# Powersupply_V1_10_final.net
KiCad netlist of a schematic drawn in EAGLE
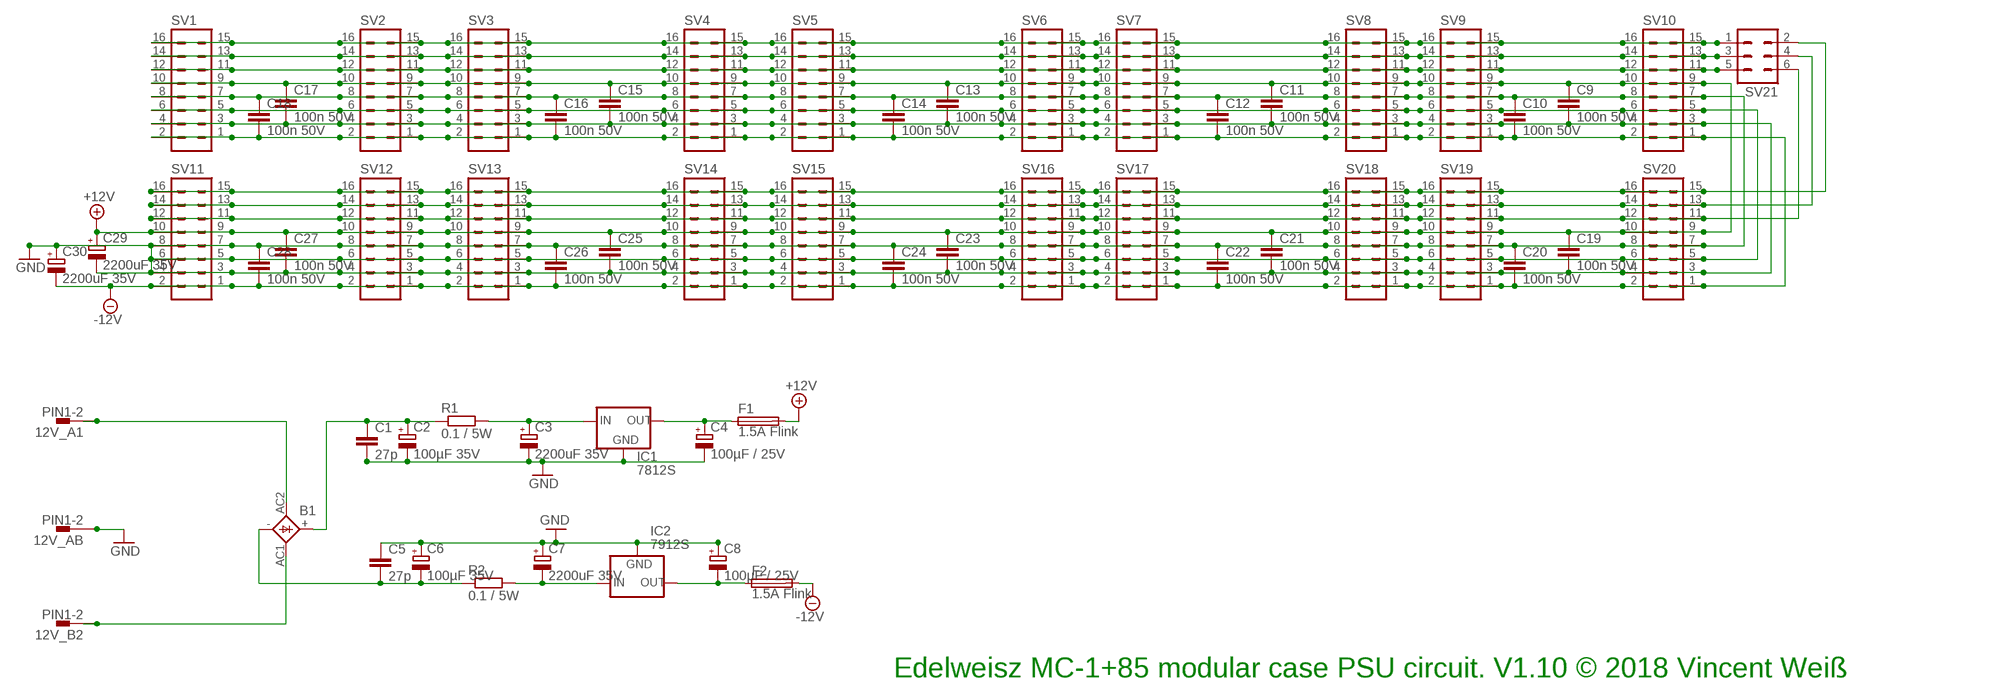
[diagram p0: schematic, sheet 1]

(export (version "E")
  (design (tool "Eeschema 10.0.6"))
  (components
    (comp (ref "12V_A1")
      (value "PIN1-2")
      (footprint "eagle-import:62221")
      (fields (field (name "MF") "TYCO ELECTRONICS") (field (name "MPN") "62221-1"))
      (libsource (lib "eagle-import") (part "PIN1-2"))
    )
    (comp (ref "12V_AB")
      (value "PIN1-2")
      (footprint "eagle-import:62221")
      (fields (field (name "MF") "TYCO ELECTRONICS") (field (name "MPN") "62221-1"))
      (libsource (lib "eagle-import") (part "PIN1-2"))
    )
    (comp (ref "12V_B2")
      (value "PIN1-2")
      (footprint "eagle-import:62221")
      (fields (field (name "MF") "TYCO ELECTRONICS") (field (name "MPN") "62221-1"))
      (libsource (lib "eagle-import") (part "PIN1-2"))
    )
    (comp (ref "B1")
      (value "GBU4")
      (footprint "eagle-import:GBU4S")
      (libsource (lib "eagle-import") (part "GBU4"))
    )
    (comp (ref "C1")
      (value "27p")
      (footprint "eagle-import:C050-024X044")
      (libsource (lib "eagle-import") (part "C-EU050-024X044"))
    )
    (comp (ref "C2")
      (value "100µF 35V")
      (footprint "eagle-import:E2,5-7")
      (libsource (lib "eagle-import") (part "CPOL-EUE2.5-7"))
    )
    (comp (ref "C3")
      (value "2200uF 35V")
      (footprint "eagle-import:E7,5-16")
      (libsource (lib "eagle-import") (part "CPOL-EUE7.5-16"))
    )
    (comp (ref "C4")
      (value "100µF / 25V")
      (footprint "eagle-import:E2,5-7")
      (libsource (lib "eagle-import") (part "CPOL-EUE2.5-7"))
    )
    (comp (ref "C5")
      (value "27p")
      (footprint "eagle-import:C050-024X044")
      (libsource (lib "eagle-import") (part "C-EU050-024X044"))
    )
    (comp (ref "C6")
      (value "100µF 35V")
      (footprint "eagle-import:E2,5-7")
      (libsource (lib "eagle-import") (part "CPOL-EUE2.5-7"))
    )
    (comp (ref "C7")
      (value "2200uF 35V")
      (footprint "eagle-import:E7,5-16")
      (libsource (lib "eagle-import") (part "CPOL-EUE7.5-16"))
    )
    (comp (ref "C8")
      (value "100µF / 25V")
      (footprint "eagle-import:E2,5-7")
      (libsource (lib "eagle-import") (part "CPOL-EUE2.5-7"))
    )
    (comp (ref "C9")
      (value "100n 50V")
      (footprint "eagle-import:C025-025X050")
      (libsource (lib "eagle-import") (part "C-EU025-025X050"))
    )
    (comp (ref "C10")
      (value "100n 50V")
      (footprint "eagle-import:C025-025X050")
      (libsource (lib "eagle-import") (part "C-EU025-025X050"))
    )
    (comp (ref "C11")
      (value "100n 50V")
      (footprint "eagle-import:C025-025X050")
      (libsource (lib "eagle-import") (part "C-EU025-025X050"))
    )
    (comp (ref "C12")
      (value "100n 50V")
      (footprint "eagle-import:C025-025X050")
      (libsource (lib "eagle-import") (part "C-EU025-025X050"))
    )
    (comp (ref "C13")
      (value "100n 50V")
      (footprint "eagle-import:C025-025X050")
      (libsource (lib "eagle-import") (part "C-EU025-025X050"))
    )
    (comp (ref "C14")
      (value "100n 50V")
      (footprint "eagle-import:C025-025X050")
      (libsource (lib "eagle-import") (part "C-EU025-025X050"))
    )
    (comp (ref "C15")
      (value "100n 50V")
      (footprint "eagle-import:C025-025X050")
      (libsource (lib "eagle-import") (part "C-EU025-025X050"))
    )
    (comp (ref "C16")
      (value "100n 50V")
      (footprint "eagle-import:C025-025X050")
      (libsource (lib "eagle-import") (part "C-EU025-025X050"))
    )
    (comp (ref "C17")
      (value "100n 50V")
      (footprint "eagle-import:C025-025X050")
      (libsource (lib "eagle-import") (part "C-EU025-025X050"))
    )
    (comp (ref "C18")
      (value "100n 50V")
      (footprint "eagle-import:C025-025X050")
      (libsource (lib "eagle-import") (part "C-EU025-025X050"))
    )
    (comp (ref "C19")
      (value "100n 50V")
      (footprint "eagle-import:C025-025X050")
      (libsource (lib "eagle-import") (part "C-EU025-025X050"))
    )
    (comp (ref "C20")
      (value "100n 50V")
      (footprint "eagle-import:C025-025X050")
      (libsource (lib "eagle-import") (part "C-EU025-025X050"))
    )
    (comp (ref "C21")
      (value "100n 50V")
      (footprint "eagle-import:C025-025X050")
      (libsource (lib "eagle-import") (part "C-EU025-025X050"))
    )
    (comp (ref "C22")
      (value "100n 50V")
      (footprint "eagle-import:C025-025X050")
      (libsource (lib "eagle-import") (part "C-EU025-025X050"))
    )
    (comp (ref "C23")
      (value "100n 50V")
      (footprint "eagle-import:C025-025X050")
      (libsource (lib "eagle-import") (part "C-EU025-025X050"))
    )
    (comp (ref "C24")
      (value "100n 50V")
      (footprint "eagle-import:C025-025X050")
      (libsource (lib "eagle-import") (part "C-EU025-025X050"))
    )
    (comp (ref "C25")
      (value "100n 50V")
      (footprint "eagle-import:C025-025X050")
      (libsource (lib "eagle-import") (part "C-EU025-025X050"))
    )
    (comp (ref "C26")
      (value "100n 50V")
      (footprint "eagle-import:C025-025X050")
      (libsource (lib "eagle-import") (part "C-EU025-025X050"))
    )
    (comp (ref "C27")
      (value "100n 50V")
      (footprint "eagle-import:C025-025X050")
      (libsource (lib "eagle-import") (part "C-EU025-025X050"))
    )
    (comp (ref "C28")
      (value "100n 50V")
      (footprint "eagle-import:C025-025X050")
      (libsource (lib "eagle-import") (part "C-EU025-025X050"))
    )
    (comp (ref "C29")
      (value "2200uF 35V")
      (footprint "eagle-import:E7,5-16")
      (libsource (lib "eagle-import") (part "CPOL-EUE7.5-16"))
    )
    (comp (ref "C30")
      (value "2200uF 35V")
      (footprint "eagle-import:E7,5-16")
      (libsource (lib "eagle-import") (part "CPOL-EUE7.5-16"))
    )
    (comp (ref "F1")
      (value "1.5A Flink")
      (footprint "eagle-import:SH22,5")
      (fields (field (name "MF") "SCHURTER") (field (name "MPN") "0031.8201"))
      (libsource (lib "eagle-import") (part "SH22,5"))
    )
    (comp (ref "F2")
      (value "1.5A Flink")
      (footprint "eagle-import:SH22,5")
      (fields (field (name "MF") "SCHURTER") (field (name "MPN") "0031.8201"))
      (libsource (lib "eagle-import") (part "SH22,5"))
    )
    (comp (ref "IC1")
      (value "7812S")
      (footprint "eagle-import:78XXS")
      (libsource (lib "eagle-import") (part "78XXS"))
    )
    (comp (ref "IC2")
      (value "7912S")
      (footprint "eagle-import:79XXS")
      (libsource (lib "eagle-import") (part "79XXS"))
    )
    (comp (ref "R1")
      (value "0.1 / 5W")
      (footprint "eagle-import:P0613_15")
      (libsource (lib "eagle-import") (part "R-EU_0613/15"))
    )
    (comp (ref "R2")
      (value "0.1 / 5W")
      (footprint "eagle-import:P0613_15")
      (libsource (lib "eagle-import") (part "R-EU_0613/15"))
    )
    (comp (ref "SV1")
      (value "ML16")
      (footprint "eagle-import:ML16")
      (libsource (lib "eagle-import") (part "ML16"))
    )
    (comp (ref "SV2")
      (value "ML16")
      (footprint "eagle-import:ML16")
      (libsource (lib "eagle-import") (part "ML16"))
    )
    (comp (ref "SV3")
      (value "ML16")
      (footprint "eagle-import:ML16")
      (libsource (lib "eagle-import") (part "ML16"))
    )
    (comp (ref "SV4")
      (value "ML16")
      (footprint "eagle-import:ML16")
      (libsource (lib "eagle-import") (part "ML16"))
    )
    (comp (ref "SV5")
      (value "ML16")
      (footprint "eagle-import:ML16")
      (libsource (lib "eagle-import") (part "ML16"))
    )
    (comp (ref "SV6")
      (value "ML16")
      (footprint "eagle-import:ML16")
      (libsource (lib "eagle-import") (part "ML16"))
    )
    (comp (ref "SV7")
      (value "ML16")
      (footprint "eagle-import:ML16")
      (libsource (lib "eagle-import") (part "ML16"))
    )
    (comp (ref "SV8")
      (value "ML16")
      (footprint "eagle-import:ML16")
      (libsource (lib "eagle-import") (part "ML16"))
    )
    (comp (ref "SV9")
      (value "ML16")
      (footprint "eagle-import:ML16")
      (libsource (lib "eagle-import") (part "ML16"))
    )
    (comp (ref "SV10")
      (value "ML16")
      (footprint "eagle-import:ML16")
      (libsource (lib "eagle-import") (part "ML16"))
    )
    (comp (ref "SV11")
      (value "ML16")
      (footprint "eagle-import:ML16")
      (libsource (lib "eagle-import") (part "ML16"))
    )
    (comp (ref "SV12")
      (value "ML16")
      (footprint "eagle-import:ML16")
      (libsource (lib "eagle-import") (part "ML16"))
    )
    (comp (ref "SV13")
      (value "ML16")
      (footprint "eagle-import:ML16")
      (libsource (lib "eagle-import") (part "ML16"))
    )
    (comp (ref "SV14")
      (value "ML16")
      (footprint "eagle-import:ML16")
      (libsource (lib "eagle-import") (part "ML16"))
    )
    (comp (ref "SV15")
      (value "ML16")
      (footprint "eagle-import:ML16")
      (libsource (lib "eagle-import") (part "ML16"))
    )
    (comp (ref "SV16")
      (value "ML16")
      (footprint "eagle-import:ML16")
      (libsource (lib "eagle-import") (part "ML16"))
    )
    (comp (ref "SV17")
      (value "ML16")
      (footprint "eagle-import:ML16")
      (libsource (lib "eagle-import") (part "ML16"))
    )
    (comp (ref "SV18")
      (value "ML16")
      (footprint "eagle-import:ML16")
      (libsource (lib "eagle-import") (part "ML16"))
    )
    (comp (ref "SV19")
      (value "ML16")
      (footprint "eagle-import:ML16")
      (libsource (lib "eagle-import") (part "ML16"))
    )
    (comp (ref "SV20")
      (value "ML16")
      (footprint "eagle-import:ML16")
      (libsource (lib "eagle-import") (part "ML16"))
    )
    (comp (ref "SV21")
      (value "MA03-2")
      (footprint "eagle-import:MA03-2")
      (libsource (lib "eagle-import") (part "MA03-2"))
    )
  )
  (nets
    (net (code "1") (name "+12V") (class "Default")
      (node (ref "C11") (pin "1") (pinfunction "1_1") (pintype "passive"))
      (node (ref "C13") (pin "1") (pinfunction "1_1") (pintype "passive"))
      (node (ref "C15") (pin "1") (pinfunction "1_1") (pintype "passive"))
      (node (ref "C17") (pin "1") (pinfunction "1_1") (pintype "passive"))
      (node (ref "C19") (pin "1") (pinfunction "1_1") (pintype "passive"))
      (node (ref "C21") (pin "1") (pinfunction "1_1") (pintype "passive"))
      (node (ref "C23") (pin "1") (pinfunction "1_1") (pintype "passive"))
      (node (ref "C25") (pin "1") (pinfunction "1_1") (pintype "passive"))
      (node (ref "C27") (pin "1") (pinfunction "1_1") (pintype "passive"))
      (node (ref "C29") (pin "+") (pinfunction "+_+") (pintype "passive"))
      (node (ref "C9") (pin "1") (pinfunction "1_1") (pintype "passive"))
      (node (ref "F1") (pin "2") (pinfunction "2_2") (pintype "passive"))
      (node (ref "SV1") (pin "10") (pinfunction "10_10") (pintype "passive"))
      (node (ref "SV1") (pin "9") (pinfunction "9_9") (pintype "passive"))
      (node (ref "SV10") (pin "10") (pinfunction "10_10") (pintype "passive"))
      (node (ref "SV10") (pin "9") (pinfunction "9_9") (pintype "passive"))
      (node (ref "SV11") (pin "10") (pinfunction "10_10") (pintype "passive"))
      (node (ref "SV11") (pin "9") (pinfunction "9_9") (pintype "passive"))
      (node (ref "SV12") (pin "10") (pinfunction "10_10") (pintype "passive"))
      (node (ref "SV12") (pin "9") (pinfunction "9_9") (pintype "passive"))
      (node (ref "SV13") (pin "10") (pinfunction "10_10") (pintype "passive"))
      (node (ref "SV13") (pin "9") (pinfunction "9_9") (pintype "passive"))
      (node (ref "SV14") (pin "10") (pinfunction "10_10") (pintype "passive"))
      (node (ref "SV14") (pin "9") (pinfunction "9_9") (pintype "passive"))
      (node (ref "SV15") (pin "10") (pinfunction "10_10") (pintype "passive"))
      (node (ref "SV15") (pin "9") (pinfunction "9_9") (pintype "passive"))
      (node (ref "SV16") (pin "10") (pinfunction "10_10") (pintype "passive"))
      (node (ref "SV16") (pin "9") (pinfunction "9_9") (pintype "passive"))
      (node (ref "SV17") (pin "10") (pinfunction "10_10") (pintype "passive"))
      (node (ref "SV17") (pin "9") (pinfunction "9_9") (pintype "passive"))
      (node (ref "SV18") (pin "10") (pinfunction "10_10") (pintype "passive"))
      (node (ref "SV18") (pin "9") (pinfunction "9_9") (pintype "passive"))
      (node (ref "SV19") (pin "10") (pinfunction "10_10") (pintype "passive"))
      (node (ref "SV19") (pin "9") (pinfunction "9_9") (pintype "passive"))
      (node (ref "SV2") (pin "10") (pinfunction "10_10") (pintype "passive"))
      (node (ref "SV2") (pin "9") (pinfunction "9_9") (pintype "passive"))
      (node (ref "SV20") (pin "10") (pinfunction "10_10") (pintype "passive"))
      (node (ref "SV20") (pin "9") (pinfunction "9_9") (pintype "passive"))
      (node (ref "SV3") (pin "10") (pinfunction "10_10") (pintype "passive"))
      (node (ref "SV3") (pin "9") (pinfunction "9_9") (pintype "passive"))
      (node (ref "SV4") (pin "10") (pinfunction "10_10") (pintype "passive"))
      (node (ref "SV4") (pin "9") (pinfunction "9_9") (pintype "passive"))
      (node (ref "SV5") (pin "10") (pinfunction "10_10") (pintype "passive"))
      (node (ref "SV5") (pin "9") (pinfunction "9_9") (pintype "passive"))
      (node (ref "SV6") (pin "10") (pinfunction "10_10") (pintype "passive"))
      (node (ref "SV6") (pin "9") (pinfunction "9_9") (pintype "passive"))
      (node (ref "SV7") (pin "10") (pinfunction "10_10") (pintype "passive"))
      (node (ref "SV7") (pin "9") (pinfunction "9_9") (pintype "passive"))
      (node (ref "SV8") (pin "10") (pinfunction "10_10") (pintype "passive"))
      (node (ref "SV8") (pin "9") (pinfunction "9_9") (pintype "passive"))
      (node (ref "SV9") (pin "10") (pinfunction "10_10") (pintype "passive"))
      (node (ref "SV9") (pin "9") (pinfunction "9_9") (pintype "passive"))
    )
    (net (code "2") (name "-12V") (class "Default")
      (node (ref "C10") (pin "2") (pinfunction "2_2") (pintype "passive"))
      (node (ref "C12") (pin "2") (pinfunction "2_2") (pintype "passive"))
      (node (ref "C14") (pin "2") (pinfunction "2_2") (pintype "passive"))
      (node (ref "C16") (pin "2") (pinfunction "2_2") (pintype "passive"))
      (node (ref "C18") (pin "2") (pinfunction "2_2") (pintype "passive"))
      (node (ref "C20") (pin "2") (pinfunction "2_2") (pintype "passive"))
      (node (ref "C22") (pin "2") (pinfunction "2_2") (pintype "passive"))
      (node (ref "C24") (pin "2") (pinfunction "2_2") (pintype "passive"))
      (node (ref "C26") (pin "2") (pinfunction "2_2") (pintype "passive"))
      (node (ref "C28") (pin "2") (pinfunction "2_2") (pintype "passive"))
      (node (ref "C30") (pin "-") (pinfunction "-_-") (pintype "passive"))
      (node (ref "F2") (pin "2") (pinfunction "2_2") (pintype "passive"))
      (node (ref "SV1") (pin "1") (pinfunction "1_1") (pintype "passive"))
      (node (ref "SV1") (pin "2") (pinfunction "2_2") (pintype "passive"))
      (node (ref "SV10") (pin "1") (pinfunction "1_1") (pintype "passive"))
      (node (ref "SV10") (pin "2") (pinfunction "2_2") (pintype "passive"))
      (node (ref "SV11") (pin "1") (pinfunction "1_1") (pintype "passive"))
      (node (ref "SV11") (pin "2") (pinfunction "2_2") (pintype "passive"))
      (node (ref "SV12") (pin "1") (pinfunction "1_1") (pintype "passive"))
      (node (ref "SV12") (pin "2") (pinfunction "2_2") (pintype "passive"))
      (node (ref "SV13") (pin "1") (pinfunction "1_1") (pintype "passive"))
      (node (ref "SV13") (pin "2") (pinfunction "2_2") (pintype "passive"))
      (node (ref "SV14") (pin "1") (pinfunction "1_1") (pintype "passive"))
      (node (ref "SV14") (pin "2") (pinfunction "2_2") (pintype "passive"))
      (node (ref "SV15") (pin "1") (pinfunction "1_1") (pintype "passive"))
      (node (ref "SV15") (pin "2") (pinfunction "2_2") (pintype "passive"))
      (node (ref "SV16") (pin "1") (pinfunction "1_1") (pintype "passive"))
      (node (ref "SV16") (pin "2") (pinfunction "2_2") (pintype "passive"))
      (node (ref "SV17") (pin "1") (pinfunction "1_1") (pintype "passive"))
      (node (ref "SV17") (pin "2") (pinfunction "2_2") (pintype "passive"))
      (node (ref "SV18") (pin "1") (pinfunction "1_1") (pintype "passive"))
      (node (ref "SV18") (pin "2") (pinfunction "2_2") (pintype "passive"))
      (node (ref "SV19") (pin "1") (pinfunction "1_1") (pintype "passive"))
      (node (ref "SV19") (pin "2") (pinfunction "2_2") (pintype "passive"))
      (node (ref "SV2") (pin "1") (pinfunction "1_1") (pintype "passive"))
      (node (ref "SV2") (pin "2") (pinfunction "2_2") (pintype "passive"))
      (node (ref "SV20") (pin "1") (pinfunction "1_1") (pintype "passive"))
      (node (ref "SV20") (pin "2") (pinfunction "2_2") (pintype "passive"))
      (node (ref "SV3") (pin "1") (pinfunction "1_1") (pintype "passive"))
      (node (ref "SV3") (pin "2") (pinfunction "2_2") (pintype "passive"))
      (node (ref "SV4") (pin "1") (pinfunction "1_1") (pintype "passive"))
      (node (ref "SV4") (pin "2") (pinfunction "2_2") (pintype "passive"))
      (node (ref "SV5") (pin "1") (pinfunction "1_1") (pintype "passive"))
      (node (ref "SV5") (pin "2") (pinfunction "2_2") (pintype "passive"))
      (node (ref "SV6") (pin "1") (pinfunction "1_1") (pintype "passive"))
      (node (ref "SV6") (pin "2") (pinfunction "2_2") (pintype "passive"))
      (node (ref "SV7") (pin "1") (pinfunction "1_1") (pintype "passive"))
      (node (ref "SV7") (pin "2") (pinfunction "2_2") (pintype "passive"))
      (node (ref "SV8") (pin "1") (pinfunction "1_1") (pintype "passive"))
      (node (ref "SV8") (pin "2") (pinfunction "2_2") (pintype "passive"))
      (node (ref "SV9") (pin "1") (pinfunction "1_1") (pintype "passive"))
      (node (ref "SV9") (pin "2") (pinfunction "2_2") (pintype "passive"))
    )
    (net (code "3") (name "GND") (class "Default")
      (node (ref "12V_AB") (pin "1") (pinfunction "1_1") (pintype "passive"))
      (node (ref "C1") (pin "2") (pinfunction "2_2") (pintype "passive"))
      (node (ref "C10") (pin "1") (pinfunction "1_1") (pintype "passive"))
      (node (ref "C11") (pin "2") (pinfunction "2_2") (pintype "passive"))
      (node (ref "C12") (pin "1") (pinfunction "1_1") (pintype "passive"))
      (node (ref "C13") (pin "2") (pinfunction "2_2") (pintype "passive"))
      (node (ref "C14") (pin "1") (pinfunction "1_1") (pintype "passive"))
      (node (ref "C15") (pin "2") (pinfunction "2_2") (pintype "passive"))
      (node (ref "C16") (pin "1") (pinfunction "1_1") (pintype "passive"))
      (node (ref "C17") (pin "2") (pinfunction "2_2") (pintype "passive"))
      (node (ref "C18") (pin "1") (pinfunction "1_1") (pintype "passive"))
      (node (ref "C19") (pin "2") (pinfunction "2_2") (pintype "passive"))
      (node (ref "C2") (pin "-") (pinfunction "-_-") (pintype "passive"))
      (node (ref "C20") (pin "1") (pinfunction "1_1") (pintype "passive"))
      (node (ref "C21") (pin "2") (pinfunction "2_2") (pintype "passive"))
      (node (ref "C22") (pin "1") (pinfunction "1_1") (pintype "passive"))
      (node (ref "C23") (pin "2") (pinfunction "2_2") (pintype "passive"))
      (node (ref "C24") (pin "1") (pinfunction "1_1") (pintype "passive"))
      (node (ref "C25") (pin "2") (pinfunction "2_2") (pintype "passive"))
      (node (ref "C26") (pin "1") (pinfunction "1_1") (pintype "passive"))
      (node (ref "C27") (pin "2") (pinfunction "2_2") (pintype "passive"))
      (node (ref "C28") (pin "1") (pinfunction "1_1") (pintype "passive"))
      (node (ref "C29") (pin "-") (pinfunction "-_-") (pintype "passive"))
      (node (ref "C3") (pin "-") (pinfunction "-_-") (pintype "passive"))
      (node (ref "C30") (pin "+") (pinfunction "+_+") (pintype "passive"))
      (node (ref "C4") (pin "-") (pinfunction "-_-") (pintype "passive"))
      (node (ref "C5") (pin "1") (pinfunction "1_1") (pintype "passive"))
      (node (ref "C6") (pin "+") (pinfunction "+_+") (pintype "passive"))
      (node (ref "C7") (pin "+") (pinfunction "+_+") (pintype "passive"))
      (node (ref "C8") (pin "+") (pinfunction "+_+") (pintype "passive"))
      (node (ref "C9") (pin "2") (pinfunction "2_2") (pintype "passive"))
      (node (ref "IC1") (pin "GND") (pinfunction "GND_GND") (pintype "input"))
      (node (ref "IC2") (pin "GND") (pinfunction "GND_GND") (pintype "input"))
      (node (ref "SV1") (pin "3") (pinfunction "3_3") (pintype "passive"))
      (node (ref "SV1") (pin "4") (pinfunction "4_4") (pintype "passive"))
      (node (ref "SV1") (pin "5") (pinfunction "5_5") (pintype "passive"))
      (node (ref "SV1") (pin "6") (pinfunction "6_6") (pintype "passive"))
      (node (ref "SV1") (pin "7") (pinfunction "7_7") (pintype "passive"))
      (node (ref "SV1") (pin "8") (pinfunction "8_8") (pintype "passive"))
      (node (ref "SV10") (pin "3") (pinfunction "3_3") (pintype "passive"))
      (node (ref "SV10") (pin "4") (pinfunction "4_4") (pintype "passive"))
      (node (ref "SV10") (pin "5") (pinfunction "5_5") (pintype "passive"))
      (node (ref "SV10") (pin "6") (pinfunction "6_6") (pintype "passive"))
      (node (ref "SV10") (pin "7") (pinfunction "7_7") (pintype "passive"))
      (node (ref "SV10") (pin "8") (pinfunction "8_8") (pintype "passive"))
      (node (ref "SV11") (pin "3") (pinfunction "3_3") (pintype "passive"))
      (node (ref "SV11") (pin "4") (pinfunction "4_4") (pintype "passive"))
      (node (ref "SV11") (pin "5") (pinfunction "5_5") (pintype "passive"))
      (node (ref "SV11") (pin "6") (pinfunction "6_6") (pintype "passive"))
      (node (ref "SV11") (pin "7") (pinfunction "7_7") (pintype "passive"))
      (node (ref "SV11") (pin "8") (pinfunction "8_8") (pintype "passive"))
      (node (ref "SV12") (pin "3") (pinfunction "3_3") (pintype "passive"))
      (node (ref "SV12") (pin "4") (pinfunction "4_4") (pintype "passive"))
      (node (ref "SV12") (pin "5") (pinfunction "5_5") (pintype "passive"))
      (node (ref "SV12") (pin "6") (pinfunction "6_6") (pintype "passive"))
      (node (ref "SV12") (pin "7") (pinfunction "7_7") (pintype "passive"))
      (node (ref "SV12") (pin "8") (pinfunction "8_8") (pintype "passive"))
      (node (ref "SV13") (pin "3") (pinfunction "3_3") (pintype "passive"))
      (node (ref "SV13") (pin "4") (pinfunction "4_4") (pintype "passive"))
      (node (ref "SV13") (pin "5") (pinfunction "5_5") (pintype "passive"))
      (node (ref "SV13") (pin "6") (pinfunction "6_6") (pintype "passive"))
      (node (ref "SV13") (pin "7") (pinfunction "7_7") (pintype "passive"))
      (node (ref "SV13") (pin "8") (pinfunction "8_8") (pintype "passive"))
      (node (ref "SV14") (pin "3") (pinfunction "3_3") (pintype "passive"))
      (node (ref "SV14") (pin "4") (pinfunction "4_4") (pintype "passive"))
      (node (ref "SV14") (pin "5") (pinfunction "5_5") (pintype "passive"))
      (node (ref "SV14") (pin "6") (pinfunction "6_6") (pintype "passive"))
      (node (ref "SV14") (pin "7") (pinfunction "7_7") (pintype "passive"))
      (node (ref "SV14") (pin "8") (pinfunction "8_8") (pintype "passive"))
      (node (ref "SV15") (pin "3") (pinfunction "3_3") (pintype "passive"))
      (node (ref "SV15") (pin "4") (pinfunction "4_4") (pintype "passive"))
      (node (ref "SV15") (pin "5") (pinfunction "5_5") (pintype "passive"))
      (node (ref "SV15") (pin "6") (pinfunction "6_6") (pintype "passive"))
      (node (ref "SV15") (pin "7") (pinfunction "7_7") (pintype "passive"))
      (node (ref "SV15") (pin "8") (pinfunction "8_8") (pintype "passive"))
      (node (ref "SV16") (pin "3") (pinfunction "3_3") (pintype "passive"))
      (node (ref "SV16") (pin "4") (pinfunction "4_4") (pintype "passive"))
      (node (ref "SV16") (pin "5") (pinfunction "5_5") (pintype "passive"))
      (node (ref "SV16") (pin "6") (pinfunction "6_6") (pintype "passive"))
      (node (ref "SV16") (pin "7") (pinfunction "7_7") (pintype "passive"))
      (node (ref "SV16") (pin "8") (pinfunction "8_8") (pintype "passive"))
      (node (ref "SV17") (pin "3") (pinfunction "3_3") (pintype "passive"))
      (node (ref "SV17") (pin "4") (pinfunction "4_4") (pintype "passive"))
      (node (ref "SV17") (pin "5") (pinfunction "5_5") (pintype "passive"))
      (node (ref "SV17") (pin "6") (pinfunction "6_6") (pintype "passive"))
      (node (ref "SV17") (pin "7") (pinfunction "7_7") (pintype "passive"))
      (node (ref "SV17") (pin "8") (pinfunction "8_8") (pintype "passive"))
      (node (ref "SV18") (pin "3") (pinfunction "3_3") (pintype "passive"))
      (node (ref "SV18") (pin "4") (pinfunction "4_4") (pintype "passive"))
      (node (ref "SV18") (pin "5") (pinfunction "5_5") (pintype "passive"))
      (node (ref "SV18") (pin "6") (pinfunction "6_6") (pintype "passive"))
      (node (ref "SV18") (pin "7") (pinfunction "7_7") (pintype "passive"))
      (node (ref "SV18") (pin "8") (pinfunction "8_8") (pintype "passive"))
      (node (ref "SV19") (pin "3") (pinfunction "3_3") (pintype "passive"))
      (node (ref "SV19") (pin "4") (pinfunction "4_4") (pintype "passive"))
      (node (ref "SV19") (pin "5") (pinfunction "5_5") (pintype "passive"))
      (node (ref "SV19") (pin "6") (pinfunction "6_6") (pintype "passive"))
      (node (ref "SV19") (pin "7") (pinfunction "7_7") (pintype "passive"))
      (node (ref "SV19") (pin "8") (pinfunction "8_8") (pintype "passive"))
      (node (ref "SV2") (pin "3") (pinfunction "3_3") (pintype "passive"))
      (node (ref "SV2") (pin "4") (pinfunction "4_4") (pintype "passive"))
      (node (ref "SV2") (pin "5") (pinfunction "5_5") (pintype "passive"))
      (node (ref "SV2") (pin "6") (pinfunction "6_6") (pintype "passive"))
      (node (ref "SV2") (pin "7") (pinfunction "7_7") (pintype "passive"))
      (node (ref "SV2") (pin "8") (pinfunction "8_8") (pintype "passive"))
      (node (ref "SV20") (pin "3") (pinfunction "3_3") (pintype "passive"))
      (node (ref "SV20") (pin "4") (pinfunction "4_4") (pintype "passive"))
      (node (ref "SV20") (pin "5") (pinfunction "5_5") (pintype "passive"))
      (node (ref "SV20") (pin "6") (pinfunction "6_6") (pintype "passive"))
      (node (ref "SV20") (pin "7") (pinfunction "7_7") (pintype "passive"))
      (node (ref "SV20") (pin "8") (pinfunction "8_8") (pintype "passive"))
      (node (ref "SV3") (pin "3") (pinfunction "3_3") (pintype "passive"))
      (node (ref "SV3") (pin "4") (pinfunction "4_4") (pintype "passive"))
      (node (ref "SV3") (pin "5") (pinfunction "5_5") (pintype "passive"))
      (node (ref "SV3") (pin "6") (pinfunction "6_6") (pintype "passive"))
      (node (ref "SV3") (pin "7") (pinfunction "7_7") (pintype "passive"))
      (node (ref "SV3") (pin "8") (pinfunction "8_8") (pintype "passive"))
      (node (ref "SV4") (pin "3") (pinfunction "3_3") (pintype "passive"))
      (node (ref "SV4") (pin "4") (pinfunction "4_4") (pintype "passive"))
      (node (ref "SV4") (pin "5") (pinfunction "5_5") (pintype "passive"))
      (node (ref "SV4") (pin "6") (pinfunction "6_6") (pintype "passive"))
      (node (ref "SV4") (pin "7") (pinfunction "7_7") (pintype "passive"))
      (node (ref "SV4") (pin "8") (pinfunction "8_8") (pintype "passive"))
      (node (ref "SV5") (pin "3") (pinfunction "3_3") (pintype "passive"))
      (node (ref "SV5") (pin "4") (pinfunction "4_4") (pintype "passive"))
      (node (ref "SV5") (pin "5") (pinfunction "5_5") (pintype "passive"))
      (node (ref "SV5") (pin "6") (pinfunction "6_6") (pintype "passive"))
      (node (ref "SV5") (pin "7") (pinfunction "7_7") (pintype "passive"))
      (node (ref "SV5") (pin "8") (pinfunction "8_8") (pintype "passive"))
      (node (ref "SV6") (pin "3") (pinfunction "3_3") (pintype "passive"))
      (node (ref "SV6") (pin "4") (pinfunction "4_4") (pintype "passive"))
      (node (ref "SV6") (pin "5") (pinfunction "5_5") (pintype "passive"))
      (node (ref "SV6") (pin "6") (pinfunction "6_6") (pintype "passive"))
      (node (ref "SV6") (pin "7") (pinfunction "7_7") (pintype "passive"))
      (node (ref "SV6") (pin "8") (pinfunction "8_8") (pintype "passive"))
      (node (ref "SV7") (pin "3") (pinfunction "3_3") (pintype "passive"))
      (node (ref "SV7") (pin "4") (pinfunction "4_4") (pintype "passive"))
      (node (ref "SV7") (pin "5") (pinfunction "5_5") (pintype "passive"))
      (node (ref "SV7") (pin "6") (pinfunction "6_6") (pintype "passive"))
      (node (ref "SV7") (pin "7") (pinfunction "7_7") (pintype "passive"))
      (node (ref "SV7") (pin "8") (pinfunction "8_8") (pintype "passive"))
      (node (ref "SV8") (pin "3") (pinfunction "3_3") (pintype "passive"))
      (node (ref "SV8") (pin "4") (pinfunction "4_4") (pintype "passive"))
      (node (ref "SV8") (pin "5") (pinfunction "5_5") (pintype "passive"))
      (node (ref "SV8") (pin "6") (pinfunction "6_6") (pintype "passive"))
      (node (ref "SV8") (pin "7") (pinfunction "7_7") (pintype "passive"))
      (node (ref "SV8") (pin "8") (pinfunction "8_8") (pintype "passive"))
      (node (ref "SV9") (pin "3") (pinfunction "3_3") (pintype "passive"))
      (node (ref "SV9") (pin "4") (pinfunction "4_4") (pintype "passive"))
      (node (ref "SV9") (pin "5") (pinfunction "5_5") (pintype "passive"))
      (node (ref "SV9") (pin "6") (pinfunction "6_6") (pintype "passive"))
      (node (ref "SV9") (pin "7") (pinfunction "7_7") (pintype "passive"))
      (node (ref "SV9") (pin "8") (pinfunction "8_8") (pintype "passive"))
    )
    (net (code "4") (name "Net-(B1-AC1)") (class "Default")
      (node (ref "12V_A1") (pin "1") (pinfunction "1_1") (pintype "passive"))
      (node (ref "B1") (pin "AC2") (pinfunction "AC1_AC2") (pintype "passive"))
    )
    (net (code "5") (name "Net-(B1-AC2)") (class "Default")
      (node (ref "12V_B2") (pin "1") (pinfunction "1_1") (pintype "passive"))
      (node (ref "B1") (pin "AC1") (pinfunction "AC2_AC1") (pintype "passive"))
    )
    (net (code "6") (name "Net-(B1-Pad+)") (class "Default")
      (node (ref "B1") (pin "+") (pinfunction "+_+") (pintype "passive"))
      (node (ref "C1") (pin "1") (pinfunction "1_1") (pintype "passive"))
      (node (ref "C2") (pin "+") (pinfunction "+_+") (pintype "passive"))
      (node (ref "R1") (pin "1") (pinfunction "1_1") (pintype "passive"))
    )
    (net (code "7") (name "Net-(B1-Pad-)") (class "Default")
      (node (ref "B1") (pin "-") (pinfunction "-_-") (pintype "passive"))
      (node (ref "C5") (pin "2") (pinfunction "2_2") (pintype "passive"))
      (node (ref "C6") (pin "-") (pinfunction "-_-") (pintype "passive"))
      (node (ref "R2") (pin "1") (pinfunction "1_1") (pintype "passive"))
    )
    (net (code "8") (name "Net-(C3-Pad+)") (class "Default")
      (node (ref "C3") (pin "+") (pinfunction "+_+") (pintype "passive"))
      (node (ref "IC1") (pin "IN") (pinfunction "IN_IN") (pintype "input"))
      (node (ref "R1") (pin "2") (pinfunction "2_2") (pintype "passive"))
    )
    (net (code "9") (name "Net-(C4-Pad+)") (class "Default")
      (node (ref "C4") (pin "+") (pinfunction "+_+") (pintype "passive"))
      (node (ref "F1") (pin "1") (pinfunction "1_1") (pintype "passive"))
      (node (ref "IC1") (pin "OUT") (pinfunction "OUT_OUT") (pintype "passive"))
    )
    (net (code "10") (name "Net-(C7-Pad-)") (class "Default")
      (node (ref "C7") (pin "-") (pinfunction "-_-") (pintype "passive"))
      (node (ref "IC2") (pin "IN") (pinfunction "IN_IN") (pintype "input"))
      (node (ref "R2") (pin "2") (pinfunction "2_2") (pintype "passive"))
    )
    (net (code "11") (name "Net-(C8-Pad-)") (class "Default")
      (node (ref "C8") (pin "-") (pinfunction "-_-") (pintype "passive"))
      (node (ref "F2") (pin "1") (pinfunction "1_1") (pintype "passive"))
      (node (ref "IC2") (pin "OUT") (pinfunction "OUT_OUT") (pintype "passive"))
    )
    (net (code "12") (name "Net-(SV1-Pad11)") (class "Default")
      (node (ref "SV1") (pin "11") (pinfunction "11_11") (pintype "passive"))
      (node (ref "SV1") (pin "12") (pinfunction "12_12") (pintype "passive"))
      (node (ref "SV10") (pin "11") (pinfunction "11_11") (pintype "passive"))
      (node (ref "SV10") (pin "12") (pinfunction "12_12") (pintype "passive"))
      (node (ref "SV2") (pin "11") (pinfunction "11_11") (pintype "passive"))
      (node (ref "SV2") (pin "12") (pinfunction "12_12") (pintype "passive"))
      (node (ref "SV21") (pin "5") (pinfunction "5_5") (pintype "passive"))
      (node (ref "SV3") (pin "11") (pinfunction "11_11") (pintype "passive"))
      (node (ref "SV3") (pin "12") (pinfunction "12_12") (pintype "passive"))
      (node (ref "SV4") (pin "11") (pinfunction "11_11") (pintype "passive"))
      (node (ref "SV4") (pin "12") (pinfunction "12_12") (pintype "passive"))
      (node (ref "SV5") (pin "11") (pinfunction "11_11") (pintype "passive"))
      (node (ref "SV5") (pin "12") (pinfunction "12_12") (pintype "passive"))
      (node (ref "SV6") (pin "11") (pinfunction "11_11") (pintype "passive"))
      (node (ref "SV6") (pin "12") (pinfunction "12_12") (pintype "passive"))
      (node (ref "SV7") (pin "11") (pinfunction "11_11") (pintype "passive"))
      (node (ref "SV7") (pin "12") (pinfunction "12_12") (pintype "passive"))
      (node (ref "SV8") (pin "11") (pinfunction "11_11") (pintype "passive"))
      (node (ref "SV8") (pin "12") (pinfunction "12_12") (pintype "passive"))
      (node (ref "SV9") (pin "11") (pinfunction "11_11") (pintype "passive"))
      (node (ref "SV9") (pin "12") (pinfunction "12_12") (pintype "passive"))
    )
    (net (code "13") (name "Net-(SV1-Pad13)") (class "Default")
      (node (ref "SV1") (pin "13") (pinfunction "13_13") (pintype "passive"))
      (node (ref "SV1") (pin "14") (pinfunction "14_14") (pintype "passive"))
      (node (ref "SV10") (pin "13") (pinfunction "13_13") (pintype "passive"))
      (node (ref "SV10") (pin "14") (pinfunction "14_14") (pintype "passive"))
      (node (ref "SV2") (pin "13") (pinfunction "13_13") (pintype "passive"))
      (node (ref "SV2") (pin "14") (pinfunction "14_14") (pintype "passive"))
      (node (ref "SV21") (pin "3") (pinfunction "3_3") (pintype "passive"))
      (node (ref "SV3") (pin "13") (pinfunction "13_13") (pintype "passive"))
      (node (ref "SV3") (pin "14") (pinfunction "14_14") (pintype "passive"))
      (node (ref "SV4") (pin "13") (pinfunction "13_13") (pintype "passive"))
      (node (ref "SV4") (pin "14") (pinfunction "14_14") (pintype "passive"))
      (node (ref "SV5") (pin "13") (pinfunction "13_13") (pintype "passive"))
      (node (ref "SV5") (pin "14") (pinfunction "14_14") (pintype "passive"))
      (node (ref "SV6") (pin "13") (pinfunction "13_13") (pintype "passive"))
      (node (ref "SV6") (pin "14") (pinfunction "14_14") (pintype "passive"))
      (node (ref "SV7") (pin "13") (pinfunction "13_13") (pintype "passive"))
      (node (ref "SV7") (pin "14") (pinfunction "14_14") (pintype "passive"))
      (node (ref "SV8") (pin "13") (pinfunction "13_13") (pintype "passive"))
      (node (ref "SV8") (pin "14") (pinfunction "14_14") (pintype "passive"))
      (node (ref "SV9") (pin "13") (pinfunction "13_13") (pintype "passive"))
      (node (ref "SV9") (pin "14") (pinfunction "14_14") (pintype "passive"))
    )
    (net (code "14") (name "Net-(SV1-Pad15)") (class "Default")
      (node (ref "SV1") (pin "15") (pinfunction "15_15") (pintype "passive"))
      (node (ref "SV1") (pin "16") (pinfunction "16_16") (pintype "passive"))
      (node (ref "SV10") (pin "15") (pinfunction "15_15") (pintype "passive"))
      (node (ref "SV10") (pin "16") (pinfunction "16_16") (pintype "passive"))
      (node (ref "SV2") (pin "15") (pinfunction "15_15") (pintype "passive"))
      (node (ref "SV2") (pin "16") (pinfunction "16_16") (pintype "passive"))
      (node (ref "SV21") (pin "1") (pinfunction "1_1") (pintype "passive"))
      (node (ref "SV3") (pin "15") (pinfunction "15_15") (pintype "passive"))
      (node (ref "SV3") (pin "16") (pinfunction "16_16") (pintype "passive"))
      (node (ref "SV4") (pin "15") (pinfunction "15_15") (pintype "passive"))
      (node (ref "SV4") (pin "16") (pinfunction "16_16") (pintype "passive"))
      (node (ref "SV5") (pin "15") (pinfunction "15_15") (pintype "passive"))
      (node (ref "SV5") (pin "16") (pinfunction "16_16") (pintype "passive"))
      (node (ref "SV6") (pin "15") (pinfunction "15_15") (pintype "passive"))
      (node (ref "SV6") (pin "16") (pinfunction "16_16") (pintype "passive"))
      (node (ref "SV7") (pin "15") (pinfunction "15_15") (pintype "passive"))
      (node (ref "SV7") (pin "16") (pinfunction "16_16") (pintype "passive"))
      (node (ref "SV8") (pin "15") (pinfunction "15_15") (pintype "passive"))
      (node (ref "SV8") (pin "16") (pinfunction "16_16") (pintype "passive"))
      (node (ref "SV9") (pin "15") (pinfunction "15_15") (pintype "passive"))
      (node (ref "SV9") (pin "16") (pinfunction "16_16") (pintype "passive"))
    )
    (net (code "15") (name "Net-(SV11-Pad11)") (class "Default")
      (node (ref "SV11") (pin "11") (pinfunction "11_11") (pintype "passive"))
      (node (ref "SV11") (pin "12") (pinfunction "12_12") (pintype "passive"))
      (node (ref "SV12") (pin "11") (pinfunction "11_11") (pintype "passive"))
      (node (ref "SV12") (pin "12") (pinfunction "12_12") (pintype "passive"))
      (node (ref "SV13") (pin "11") (pinfunction "11_11") (pintype "passive"))
      (node (ref "SV13") (pin "12") (pinfunction "12_12") (pintype "passive"))
      (node (ref "SV14") (pin "11") (pinfunction "11_11") (pintype "passive"))
      (node (ref "SV14") (pin "12") (pinfunction "12_12") (pintype "passive"))
      (node (ref "SV15") (pin "11") (pinfunction "11_11") (pintype "passive"))
      (node (ref "SV15") (pin "12") (pinfunction "12_12") (pintype "passive"))
      (node (ref "SV16") (pin "11") (pinfunction "11_11") (pintype "passive"))
      (node (ref "SV16") (pin "12") (pinfunction "12_12") (pintype "passive"))
      (node (ref "SV17") (pin "11") (pinfunction "11_11") (pintype "passive"))
      (node (ref "SV17") (pin "12") (pinfunction "12_12") (pintype "passive"))
      (node (ref "SV18") (pin "11") (pinfunction "11_11") (pintype "passive"))
      (node (ref "SV18") (pin "12") (pinfunction "12_12") (pintype "passive"))
      (node (ref "SV19") (pin "11") (pinfunction "11_11") (pintype "passive"))
      (node (ref "SV19") (pin "12") (pinfunction "12_12") (pintype "passive"))
      (node (ref "SV20") (pin "11") (pinfunction "11_11") (pintype "passive"))
      (node (ref "SV20") (pin "12") (pinfunction "12_12") (pintype "passive"))
      (node (ref "SV21") (pin "6") (pinfunction "6_6") (pintype "passive"))
    )
    (net (code "16") (name "Net-(SV11-Pad13)") (class "Default")
      (node (ref "SV11") (pin "13") (pinfunction "13_13") (pintype "passive"))
      (node (ref "SV11") (pin "14") (pinfunction "14_14") (pintype "passive"))
      (node (ref "SV12") (pin "13") (pinfunction "13_13") (pintype "passive"))
      (node (ref "SV12") (pin "14") (pinfunction "14_14") (pintype "passive"))
      (node (ref "SV13") (pin "13") (pinfunction "13_13") (pintype "passive"))
      (node (ref "SV13") (pin "14") (pinfunction "14_14") (pintype "passive"))
      (node (ref "SV14") (pin "13") (pinfunction "13_13") (pintype "passive"))
      (node (ref "SV14") (pin "14") (pinfunction "14_14") (pintype "passive"))
      (node (ref "SV15") (pin "13") (pinfunction "13_13") (pintype "passive"))
      (node (ref "SV15") (pin "14") (pinfunction "14_14") (pintype "passive"))
      (node (ref "SV16") (pin "13") (pinfunction "13_13") (pintype "passive"))
      (node (ref "SV16") (pin "14") (pinfunction "14_14") (pintype "passive"))
      (node (ref "SV17") (pin "13") (pinfunction "13_13") (pintype "passive"))
      (node (ref "SV17") (pin "14") (pinfunction "14_14") (pintype "passive"))
      (node (ref "SV18") (pin "13") (pinfunction "13_13") (pintype "passive"))
      (node (ref "SV18") (pin "14") (pinfunction "14_14") (pintype "passive"))
      (node (ref "SV19") (pin "13") (pinfunction "13_13") (pintype "passive"))
      (node (ref "SV19") (pin "14") (pinfunction "14_14") (pintype "passive"))
      (node (ref "SV20") (pin "13") (pinfunction "13_13") (pintype "passive"))
      (node (ref "SV20") (pin "14") (pinfunction "14_14") (pintype "passive"))
      (node (ref "SV21") (pin "4") (pinfunction "4_4") (pintype "passive"))
    )
    (net (code "17") (name "Net-(SV11-Pad15)") (class "Default")
      (node (ref "SV11") (pin "15") (pinfunction "15_15") (pintype "passive"))
      (node (ref "SV11") (pin "16") (pinfunction "16_16") (pintype "passive"))
      (node (ref "SV12") (pin "15") (pinfunction "15_15") (pintype "passive"))
      (node (ref "SV12") (pin "16") (pinfunction "16_16") (pintype "passive"))
      (node (ref "SV13") (pin "15") (pinfunction "15_15") (pintype "passive"))
      (node (ref "SV13") (pin "16") (pinfunction "16_16") (pintype "passive"))
      (node (ref "SV14") (pin "15") (pinfunction "15_15") (pintype "passive"))
      (node (ref "SV14") (pin "16") (pinfunction "16_16") (pintype "passive"))
      (node (ref "SV15") (pin "15") (pinfunction "15_15") (pintype "passive"))
      (node (ref "SV15") (pin "16") (pinfunction "16_16") (pintype "passive"))
      (node (ref "SV16") (pin "15") (pinfunction "15_15") (pintype "passive"))
      (node (ref "SV16") (pin "16") (pinfunction "16_16") (pintype "passive"))
      (node (ref "SV17") (pin "15") (pinfunction "15_15") (pintype "passive"))
      (node (ref "SV17") (pin "16") (pinfunction "16_16") (pintype "passive"))
      (node (ref "SV18") (pin "15") (pinfunction "15_15") (pintype "passive"))
      (node (ref "SV18") (pin "16") (pinfunction "16_16") (pintype "passive"))
      (node (ref "SV19") (pin "15") (pinfunction "15_15") (pintype "passive"))
      (node (ref "SV19") (pin "16") (pinfunction "16_16") (pintype "passive"))
      (node (ref "SV20") (pin "15") (pinfunction "15_15") (pintype "passive"))
      (node (ref "SV20") (pin "16") (pinfunction "16_16") (pintype "passive"))
      (node (ref "SV21") (pin "2") (pinfunction "2_2") (pintype "passive"))
    )
  )
)
